# mainboardv3_4.net
KiCad netlist of a schematic drawn in EAGLE
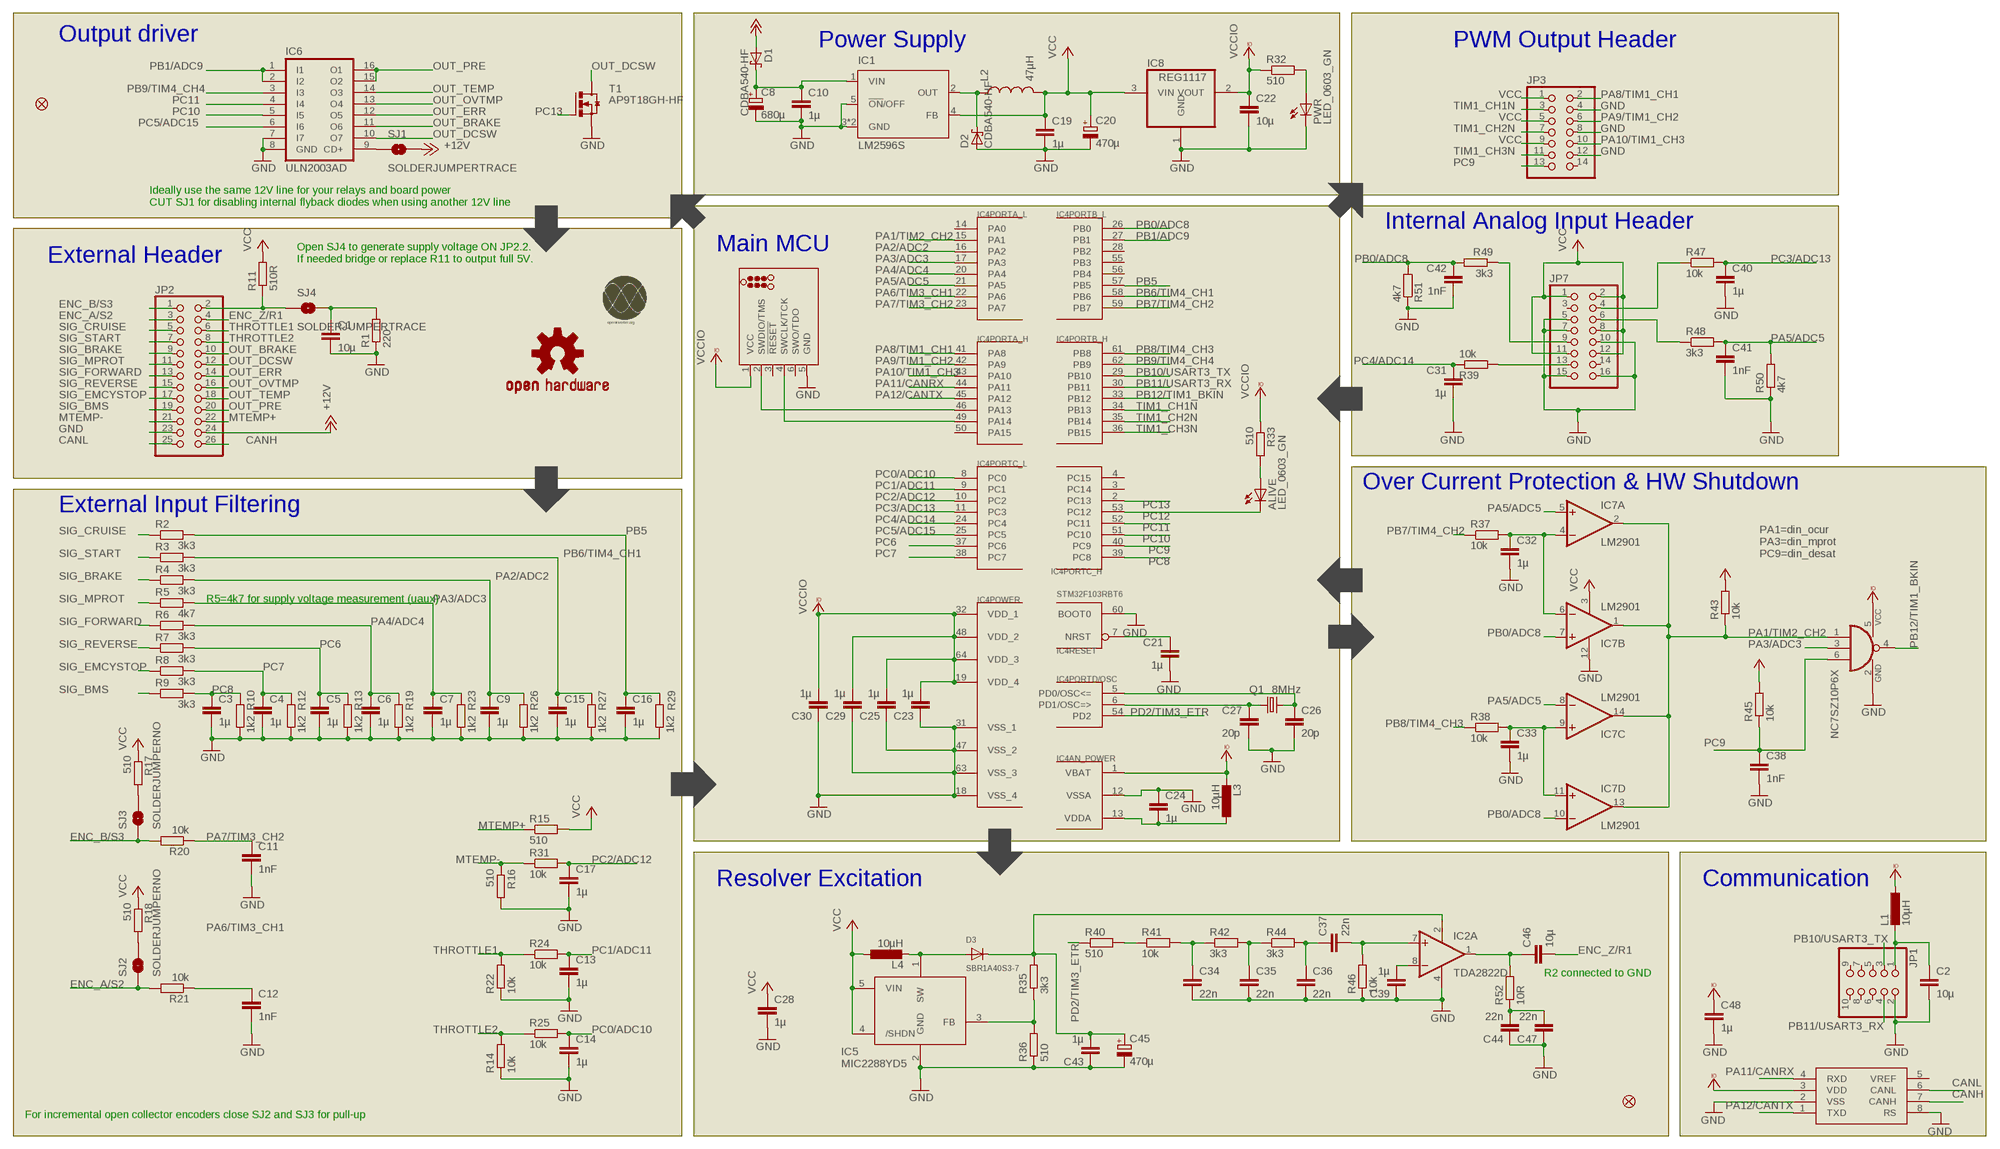
[diagram p0: schematic, sheet 1]

(export (version "E")
  (design (tool "Eeschema 10.0.6"))
  (components
    (comp (ref "ALIVE")
      (value "LED_0603_GN")
      (footprint "eagle-import:SML0805")
      (libsource (lib "eagle-import") (part "LEDSML0805"))
    )
    (comp (ref "C1")
      (value "10µ")
      (footprint "eagle-import:C0805")
      (libsource (lib "eagle-import") (part "C-EUC0805"))
    )
    (comp (ref "C2")
      (value "10µ")
      (footprint "eagle-import:C0805")
      (libsource (lib "eagle-import") (part "C-EUC0805"))
    )
    (comp (ref "C3")
      (value "1µ")
      (footprint "eagle-import:C0603")
      (libsource (lib "eagle-import") (part "C-EUC0603"))
    )
    (comp (ref "C4")
      (value "1µ")
      (footprint "eagle-import:C0603")
      (libsource (lib "eagle-import") (part "C-EUC0603"))
    )
    (comp (ref "C5")
      (value "1µ")
      (footprint "eagle-import:C0603")
      (libsource (lib "eagle-import") (part "C-EUC0603"))
    )
    (comp (ref "C6")
      (value "1µ")
      (footprint "eagle-import:C0603")
      (libsource (lib "eagle-import") (part "C-EUC0603"))
    )
    (comp (ref "C7")
      (value "1µ")
      (footprint "eagle-import:C0603")
      (libsource (lib "eagle-import") (part "C-EUC0603"))
    )
    (comp (ref "C8")
      (value "680µ")
      (footprint "eagle-import:UD-10X10_NICHICON")
      (libsource (lib "eagle-import") (part "CPOL-EUUD-10X10"))
    )
    (comp (ref "C9")
      (value "1µ")
      (footprint "eagle-import:C0603")
      (libsource (lib "eagle-import") (part "C-EUC0603"))
    )
    (comp (ref "C10")
      (value "1µ")
      (footprint "eagle-import:C0603")
      (libsource (lib "eagle-import") (part "C-EUC0603"))
    )
    (comp (ref "C11")
      (value "1nF")
      (footprint "eagle-import:C0603")
      (libsource (lib "eagle-import") (part "C-EUC0603"))
    )
    (comp (ref "C12")
      (value "1nF")
      (footprint "eagle-import:C0603")
      (libsource (lib "eagle-import") (part "C-EUC0603"))
    )
    (comp (ref "C13")
      (value "1µ")
      (footprint "eagle-import:C0603")
      (libsource (lib "eagle-import") (part "C-EUC0603"))
    )
    (comp (ref "C14")
      (value "1µ")
      (footprint "eagle-import:C0603")
      (libsource (lib "eagle-import") (part "C-EUC0603"))
    )
    (comp (ref "C15")
      (value "1µ")
      (footprint "eagle-import:C0603")
      (libsource (lib "eagle-import") (part "C-EUC0603"))
    )
    (comp (ref "C16")
      (value "1µ")
      (footprint "eagle-import:C0603")
      (libsource (lib "eagle-import") (part "C-EUC0603"))
    )
    (comp (ref "C17")
      (value "1µ")
      (footprint "eagle-import:C0603")
      (libsource (lib "eagle-import") (part "C-EUC0603"))
    )
    (comp (ref "C19")
      (value "1µ")
      (footprint "eagle-import:C0603")
      (libsource (lib "eagle-import") (part "C-EUC0603"))
    )
    (comp (ref "C20")
      (value "470µ")
      (footprint "eagle-import:UD-6,3X7,7_NICHICON")
      (libsource (lib "eagle-import") (part "CPOL-EUUD-6,3X7,7"))
    )
    (comp (ref "C21")
      (value "1µ")
      (footprint "eagle-import:C0603")
      (libsource (lib "eagle-import") (part "C-EUC0603"))
    )
    (comp (ref "C22")
      (value "10µ")
      (footprint "eagle-import:C0805")
      (libsource (lib "eagle-import") (part "C-EUC0805"))
    )
    (comp (ref "C23")
      (value "1µ")
      (footprint "eagle-import:C0603")
      (libsource (lib "eagle-import") (part "C-EUC0603"))
    )
    (comp (ref "C24")
      (value "1µ")
      (footprint "eagle-import:C0603")
      (libsource (lib "eagle-import") (part "C-EUC0603"))
    )
    (comp (ref "C25")
      (value "1µ")
      (footprint "eagle-import:C0603")
      (libsource (lib "eagle-import") (part "C-EUC0603"))
    )
    (comp (ref "C26")
      (value "20p")
      (footprint "eagle-import:C0603")
      (libsource (lib "eagle-import") (part "C-EUC0603"))
    )
    (comp (ref "C27")
      (value "20p")
      (footprint "eagle-import:C0603")
      (libsource (lib "eagle-import") (part "C-EUC0603"))
    )
    (comp (ref "C28")
      (value "1µ")
      (footprint "eagle-import:C0603")
      (libsource (lib "eagle-import") (part "C-EUC0603"))
    )
    (comp (ref "C29")
      (value "1µ")
      (footprint "eagle-import:C0603")
      (libsource (lib "eagle-import") (part "C-EUC0603"))
    )
    (comp (ref "C30")
      (value "1µ")
      (footprint "eagle-import:C0603")
      (libsource (lib "eagle-import") (part "C-EUC0603"))
    )
    (comp (ref "C31")
      (value "1µ")
      (footprint "eagle-import:C0603")
      (libsource (lib "eagle-import") (part "C-EUC0603"))
    )
    (comp (ref "C32")
      (value "1µ")
      (footprint "eagle-import:C0603")
      (libsource (lib "eagle-import") (part "C-EUC0603"))
    )
    (comp (ref "C33")
      (value "1µ")
      (footprint "eagle-import:C0603")
      (libsource (lib "eagle-import") (part "C-EUC0603"))
    )
    (comp (ref "C34")
      (value "22n")
      (footprint "eagle-import:C0603")
      (libsource (lib "eagle-import") (part "C-EUC0603"))
    )
    (comp (ref "C35")
      (value "22n")
      (footprint "eagle-import:C0603")
      (libsource (lib "eagle-import") (part "C-EUC0603"))
    )
    (comp (ref "C36")
      (value "22n")
      (footprint "eagle-import:C0603")
      (libsource (lib "eagle-import") (part "C-EUC0603"))
    )
    (comp (ref "C37")
      (value "22n")
      (footprint "eagle-import:C0603")
      (libsource (lib "eagle-import") (part "C-EUC0603"))
    )
    (comp (ref "C38")
      (value "1nF")
      (footprint "eagle-import:C0603")
      (libsource (lib "eagle-import") (part "C-EUC0603"))
    )
    (comp (ref "C39")
      (value "1µ")
      (footprint "eagle-import:C0603")
      (libsource (lib "eagle-import") (part "C-EUC0603"))
    )
    (comp (ref "C40")
      (value "1µ")
      (footprint "eagle-import:C0603")
      (libsource (lib "eagle-import") (part "C-EUC0603"))
    )
    (comp (ref "C41")
      (value "1nF")
      (footprint "eagle-import:C0603")
      (libsource (lib "eagle-import") (part "C-EUC0603"))
    )
    (comp (ref "C42")
      (value "1nF")
      (footprint "eagle-import:C0603")
      (libsource (lib "eagle-import") (part "C-EUC0603"))
    )
    (comp (ref "C43")
      (value "1µ")
      (footprint "eagle-import:C0603")
      (libsource (lib "eagle-import") (part "C-EUC0603"))
    )
    (comp (ref "C44")
      (value "22n")
      (footprint "eagle-import:C0603")
      (libsource (lib "eagle-import") (part "C-EUC0603"))
    )
    (comp (ref "C45")
      (value "470µ")
      (footprint "eagle-import:UD-6,3X7,7_NICHICON")
      (libsource (lib "eagle-import") (part "CPOL-EUUD-6,3X7,7"))
    )
    (comp (ref "C46")
      (value "10µ")
      (footprint "eagle-import:C0805")
      (libsource (lib "eagle-import") (part "C-EUC0805"))
    )
    (comp (ref "C47")
      (value "22n")
      (footprint "eagle-import:C0603")
      (libsource (lib "eagle-import") (part "C-EUC0603"))
    )
    (comp (ref "C48")
      (value "1µ")
      (footprint "eagle-import:C0603")
      (libsource (lib "eagle-import") (part "C-EUC0603"))
    )
    (comp (ref "D1")
      (value "CDBA540-HF")
      (footprint "eagle-import:SMB")
      (libsource (lib "eagle-import") (part "SCHOTTKY-DIODESMD"))
    )
    (comp (ref "D2")
      (value "CDBA540-HF")
      (footprint "eagle-import:SMB")
      (libsource (lib "eagle-import") (part "SCHOTTKY-DIODESMD"))
    )
    (comp (ref "D3")
      (value "SBR1A40S3-7")
      (footprint "eagle-import:SOD-323F")
      (libsource (lib "eagle-import") (part "DIODESOD-323F"))
    )
    (comp (ref "FID1")
      (value "FIDUCIAL1X2.5")
      (footprint "eagle-import:FIDUCIAL-1X2.5")
      (libsource (lib "eagle-import") (part "FIDUCIAL1X2.5"))
    )
    (comp (ref "FID2")
      (value "FIDUCIAL1X2.5")
      (footprint "eagle-import:FIDUCIAL-1X2.5")
      (libsource (lib "eagle-import") (part "FIDUCIAL1X2.5"))
    )
    (comp (ref "IC1")
      (value "LM2596S")
      (footprint "eagle-import:TO263-5")
      (fields (field (name "MF") "NATIONAL SEMICONDUCTOR") (field (name "MPN") "LM2596S-ADJ/NOPB"))
      (libsource (lib "eagle-import") (part "LM2596S"))
    )
    (comp (ref "IC2")
      (value "TDA2822D")
      (footprint "eagle-import:SO08")
      (libsource (lib "eagle-import") (part "TDA2822D"))
    )
    (comp (ref "IC3")
      (value "SN65HVD230DR")
      (footprint "eagle-import:SO08")
      (libsource (lib "eagle-import") (part "MCP2551"))
    )
    (comp (ref "IC4")
      (value "STM32F103RBT6")
      (footprint "eagle-import:TQFP64")
      (libsource (lib "eagle-import") (part "STM32F10XRXT6"))
    )
    (comp (ref "IC5")
      (value "MIC2288YD5")
      (footprint "eagle-import:SOT23-5L")
      (libsource (lib "eagle-import") (part "MIC2288YD5"))
    )
    (comp (ref "IC6")
      (value "ULN2003AD")
      (footprint "eagle-import:SO16")
      (libsource (lib "eagle-import") (part "ULN2003AD"))
    )
    (comp (ref "IC7")
      (value "LM2901")
      (footprint "eagle-import:SO14")
      (libsource (lib "eagle-import") (part "LM339D"))
    )
    (comp (ref "IC8")
      (value "REG1117")
      (footprint "eagle-import:SOT223")
      (libsource (lib "eagle-import") (part "REG1117"))
    )
    (comp (ref "IC9")
      (value "NC7SZ10P6X")
      (footprint "eagle-import:SC70-6")
      (libsource (lib "eagle-import") (part "741G10X"))
    )
    (comp (ref "J1")
      (value "TC2030_SWD-MCP")
      (footprint "eagle-import:TC2030-MCP")
      (libsource (lib "eagle-import") (part "TC2030_SWD-MCP"))
    )
    (comp (ref "JP1")
      (value "PINHD-2X5/90")
      (footprint "eagle-import:2X05_90")
      (libsource (lib "eagle-import") (part "PINHD-2X5/90"))
    )
    (comp (ref "JP2")
      (value "PINHD-2X13")
      (footprint "eagle-import:2X13")
      (libsource (lib "eagle-import") (part "PINHD-2X13"))
    )
    (comp (ref "JP3")
      (value "PINHD-2X7")
      (footprint "eagle-import:2X07")
      (libsource (lib "eagle-import") (part "PINHD-2X7"))
    )
    (comp (ref "JP7")
      (value "PINHD-2X8")
      (footprint "eagle-import:2X08")
      (libsource (lib "eagle-import") (part "PINHD-2X8"))
    )
    (comp (ref "L1")
      (value "10µH")
      (footprint "eagle-import:L2012C")
      (libsource (lib "eagle-import") (part "L-EUL2012C"))
    )
    (comp (ref "L2")
      (value "47µH")
      (footprint "eagle-import:CDRH125")
      (libsource (lib "eagle-import") (part "INDUCTORPWR"))
    )
    (comp (ref "L3")
      (value "10µH")
      (footprint "eagle-import:L2012C")
      (libsource (lib "eagle-import") (part "L-EUL2012C"))
    )
    (comp (ref "L4")
      (value "10µH")
      (footprint "eagle-import:L2825P")
      (libsource (lib "eagle-import") (part "L-EUL2825P"))
    )
    (comp (ref "LOGO1")
      (value "OSHW-LOGOM")
      (footprint "eagle-import:OSHW-LOGO-M")
      (libsource (lib "eagle-import") (part "OSHW-LOGOM"))
    )
    (comp (ref "PWR")
      (value "LED_0603_GN")
      (footprint "eagle-import:SML0805")
      (libsource (lib "eagle-import") (part "LEDSML0805"))
    )
    (comp (ref "Q1")
      (value "8MHz")
      (footprint "eagle-import:CRYSTAL-TXC-7A")
      (libsource (lib "eagle-import") (part "CRYSTALTXC-7A"))
    )
    (comp (ref "R1")
      (value "220")
      (footprint "eagle-import:R0603")
      (libsource (lib "eagle-import") (part "R-EU_R0603"))
    )
    (comp (ref "R2")
      (value "3k3")
      (footprint "eagle-import:R0603")
      (libsource (lib "eagle-import") (part "R-EU_R0603"))
    )
    (comp (ref "R3")
      (value "3k3")
      (footprint "eagle-import:R0603")
      (libsource (lib "eagle-import") (part "R-EU_R0603"))
    )
    (comp (ref "R4")
      (value "3k3")
      (footprint "eagle-import:R0603")
      (libsource (lib "eagle-import") (part "R-EU_R0603"))
    )
    (comp (ref "R5")
      (value "4k7")
      (footprint "eagle-import:R0603")
      (libsource (lib "eagle-import") (part "R-EU_R0603"))
    )
    (comp (ref "R6")
      (value "3k3")
      (footprint "eagle-import:R0603")
      (libsource (lib "eagle-import") (part "R-EU_R0603"))
    )
    (comp (ref "R7")
      (value "3k3")
      (footprint "eagle-import:R0603")
      (libsource (lib "eagle-import") (part "R-EU_R0603"))
    )
    (comp (ref "R8")
      (value "3k3")
      (footprint "eagle-import:R0603")
      (libsource (lib "eagle-import") (part "R-EU_R0603"))
    )
    (comp (ref "R9")
      (value "3k3")
      (footprint "eagle-import:R0603")
      (libsource (lib "eagle-import") (part "R-EU_R0603"))
    )
    (comp (ref "R10")
      (value "1k2")
      (footprint "eagle-import:R0603")
      (libsource (lib "eagle-import") (part "R-EU_R0603"))
    )
    (comp (ref "R11")
      (value "510R")
      (footprint "eagle-import:R0603")
      (libsource (lib "eagle-import") (part "R-EU_R0603"))
    )
    (comp (ref "R12")
      (value "1k2")
      (footprint "eagle-import:R0603")
      (libsource (lib "eagle-import") (part "R-EU_R0603"))
    )
    (comp (ref "R13")
      (value "1k2")
      (footprint "eagle-import:R0603")
      (libsource (lib "eagle-import") (part "R-EU_R0603"))
    )
    (comp (ref "R14")
      (value "10k")
      (footprint "eagle-import:R0603")
      (libsource (lib "eagle-import") (part "R-EU_R0603"))
    )
    (comp (ref "R15")
      (value "510")
      (footprint "eagle-import:R0603")
      (libsource (lib "eagle-import") (part "R-EU_R0603"))
    )
    (comp (ref "R16")
      (value "510")
      (footprint "eagle-import:R0603")
      (libsource (lib "eagle-import") (part "R-EU_R0603"))
    )
    (comp (ref "R17")
      (value "510")
      (footprint "eagle-import:R0603")
      (libsource (lib "eagle-import") (part "R-EU_R0603"))
    )
    (comp (ref "R18")
      (value "510")
      (footprint "eagle-import:R0603")
      (libsource (lib "eagle-import") (part "R-EU_R0603"))
    )
    (comp (ref "R19")
      (value "1k2")
      (footprint "eagle-import:R0603")
      (libsource (lib "eagle-import") (part "R-EU_R0603"))
    )
    (comp (ref "R20")
      (value "10k")
      (footprint "eagle-import:R0603")
      (libsource (lib "eagle-import") (part "R-EU_R0603"))
    )
    (comp (ref "R21")
      (value "10k")
      (footprint "eagle-import:R0603")
      (libsource (lib "eagle-import") (part "R-EU_R0603"))
    )
    (comp (ref "R22")
      (value "10k")
      (footprint "eagle-import:R0603")
      (libsource (lib "eagle-import") (part "R-EU_R0603"))
    )
    (comp (ref "R23")
      (value "1k2")
      (footprint "eagle-import:R0603")
      (libsource (lib "eagle-import") (part "R-EU_R0603"))
    )
    (comp (ref "R24")
      (value "10k")
      (footprint "eagle-import:R0603")
      (libsource (lib "eagle-import") (part "R-EU_R0603"))
    )
    (comp (ref "R25")
      (value "10k")
      (footprint "eagle-import:R0603")
      (libsource (lib "eagle-import") (part "R-EU_R0603"))
    )
    (comp (ref "R26")
      (value "1k2")
      (footprint "eagle-import:R0603")
      (libsource (lib "eagle-import") (part "R-EU_R0603"))
    )
    (comp (ref "R27")
      (value "1k2")
      (footprint "eagle-import:R0603")
      (libsource (lib "eagle-import") (part "R-EU_R0603"))
    )
    (comp (ref "R29")
      (value "1k2")
      (footprint "eagle-import:R0603")
      (libsource (lib "eagle-import") (part "R-EU_R0603"))
    )
    (comp (ref "R31")
      (value "10k")
      (footprint "eagle-import:R0603")
      (libsource (lib "eagle-import") (part "R-EU_R0603"))
    )
    (comp (ref "R32")
      (value "510")
      (footprint "eagle-import:R0603")
      (libsource (lib "eagle-import") (part "R-EU_R0603"))
    )
    (comp (ref "R33")
      (value "510")
      (footprint "eagle-import:R0603")
      (libsource (lib "eagle-import") (part "R-EU_R0603"))
    )
    (comp (ref "R35")
      (value "3k3")
      (footprint "eagle-import:R0603")
      (libsource (lib "eagle-import") (part "R-EU_R0603"))
    )
    (comp (ref "R36")
      (value "510")
      (footprint "eagle-import:R0603")
      (libsource (lib "eagle-import") (part "R-EU_R0603"))
    )
    (comp (ref "R37")
      (value "10k")
      (footprint "eagle-import:R0603")
      (libsource (lib "eagle-import") (part "R-EU_R0603"))
    )
    (comp (ref "R38")
      (value "10k")
      (footprint "eagle-import:R0603")
      (libsource (lib "eagle-import") (part "R-EU_R0603"))
    )
    (comp (ref "R39")
      (value "10k")
      (footprint "eagle-import:R0603")
      (libsource (lib "eagle-import") (part "R-EU_R0603"))
    )
    (comp (ref "R40")
      (value "510")
      (footprint "eagle-import:R0603")
      (libsource (lib "eagle-import") (part "R-EU_R0603"))
    )
    (comp (ref "R41")
      (value "10k")
      (footprint "eagle-import:R0603")
      (libsource (lib "eagle-import") (part "R-EU_R0603"))
    )
    (comp (ref "R42")
      (value "3k3")
      (footprint "eagle-import:R0603")
      (libsource (lib "eagle-import") (part "R-EU_R0603"))
    )
    (comp (ref "R43")
      (value "10k")
      (footprint "eagle-import:R0603")
      (libsource (lib "eagle-import") (part "R-EU_R0603"))
    )
    (comp (ref "R44")
      (value "3k3")
      (footprint "eagle-import:R0603")
      (libsource (lib "eagle-import") (part "R-EU_R0603"))
    )
    (comp (ref "R45")
      (value "10k")
      (footprint "eagle-import:R0603")
      (libsource (lib "eagle-import") (part "R-EU_R0603"))
    )
    (comp (ref "R46")
      (value "10k")
      (footprint "eagle-import:R0603")
      (libsource (lib "eagle-import") (part "R-EU_R0603"))
    )
    (comp (ref "R47")
      (value "10k")
      (footprint "eagle-import:R0603")
      (libsource (lib "eagle-import") (part "R-EU_R0603"))
    )
    (comp (ref "R48")
      (value "3k3")
      (footprint "eagle-import:R0603")
      (libsource (lib "eagle-import") (part "R-EU_R0603"))
    )
    (comp (ref "R49")
      (value "3k3")
      (footprint "eagle-import:R0603")
      (libsource (lib "eagle-import") (part "R-EU_R0603"))
    )
    (comp (ref "R50")
      (value "4k7")
      (footprint "eagle-import:R0603")
      (libsource (lib "eagle-import") (part "R-EU_R0603"))
    )
    (comp (ref "R51")
      (value "4k7")
      (footprint "eagle-import:R0603")
      (libsource (lib "eagle-import") (part "R-EU_R0603"))
    )
    (comp (ref "R52")
      (value "10R")
      (footprint "eagle-import:R0603")
      (libsource (lib "eagle-import") (part "R-EU_R0603"))
    )
    (comp (ref "SJ1")
      (value "SOLDERJUMPERTRACE")
      (footprint "eagle-import:SJ_2S-TRACE")
      (libsource (lib "eagle-import") (part "SOLDERJUMPERTRACE"))
    )
    (comp (ref "SJ2")
      (value "SOLDERJUMPERNO")
      (footprint "eagle-import:SJ_2S-NO")
      (libsource (lib "eagle-import") (part "SOLDERJUMPERNO"))
    )
    (comp (ref "SJ3")
      (value "SOLDERJUMPERNO")
      (footprint "eagle-import:SJ_2S-NO")
      (libsource (lib "eagle-import") (part "SOLDERJUMPERNO"))
    )
    (comp (ref "SJ4")
      (value "SOLDERJUMPERTRACE")
      (footprint "eagle-import:SJ_2S-TRACE")
      (libsource (lib "eagle-import") (part "SOLDERJUMPERTRACE"))
    )
    (comp (ref "T1")
      (value "AP9T18GH-HF")
      (footprint "eagle-import:D-PAK_TO252AA")
      (libsource (lib "eagle-import") (part "AP9T18GH-HF"))
    )
    (comp (ref "U$1")
      (value "OI-LOGO")
      (footprint "eagle-import:OI_LOGO")
      (libsource (lib "eagle-import") (part "OI-LOGO"))
    )
  )
  (nets
    (net (code "1") (name "+12V") (class "Default")
      (node (ref "D1") (pin "A") (pinfunction "A_A") (pintype "passive"))
      (node (ref "JP2") (pin "24") (pinfunction "24_24") (pintype "passive"))
      (node (ref "SJ1") (pin "2") (pinfunction "2_2") (pintype "passive"))
    )
    (net (code "2") (name "/CANH") (class "Default")
      (node (ref "IC3") (pin "7") (pinfunction "CANH_7") (pintype "bidirectional"))
      (node (ref "JP2") (pin "26") (pinfunction "26_26") (pintype "passive"))
    )
    (net (code "3") (name "/CANL") (class "Default")
      (node (ref "IC3") (pin "6") (pinfunction "CANL_6") (pintype "bidirectional"))
      (node (ref "JP2") (pin "25") (pinfunction "25_25") (pintype "passive"))
    )
    (net (code "4") (name "/ENC_A{slash}S2") (class "Default")
      (node (ref "JP2") (pin "3") (pinfunction "3_3") (pintype "passive"))
      (node (ref "R21") (pin "2") (pinfunction "2_2") (pintype "passive"))
      (node (ref "SJ2") (pin "1") (pinfunction "1_1") (pintype "passive"))
    )
    (net (code "5") (name "/ENC_B{slash}S3") (class "Default")
      (node (ref "JP2") (pin "1") (pinfunction "1_1") (pintype "passive"))
      (node (ref "R20") (pin "2") (pinfunction "2_2") (pintype "passive"))
      (node (ref "SJ3") (pin "1") (pinfunction "1_1") (pintype "passive"))
    )
    (net (code "6") (name "/ENC_Z{slash}R1") (class "Default")
      (node (ref "C46") (pin "2") (pinfunction "2_2") (pintype "passive"))
      (node (ref "JP2") (pin "4") (pinfunction "4_4") (pintype "passive"))
    )
    (net (code "7") (name "/MTEMP+") (class "Default")
      (node (ref "JP2") (pin "22") (pinfunction "22_22") (pintype "passive"))
      (node (ref "R15") (pin "1") (pinfunction "1_1") (pintype "passive"))
    )
    (net (code "8") (name "/MTEMP-") (class "Default")
      (node (ref "JP2") (pin "21") (pinfunction "21_21") (pintype "passive"))
      (node (ref "R16") (pin "1") (pinfunction "1_1") (pintype "passive"))
      (node (ref "R31") (pin "1") (pinfunction "1_1") (pintype "passive"))
    )
    (net (code "9") (name "/OUT_BRAKE") (class "Default")
      (node (ref "IC6") (pin "11") (pinfunction "O6_11") (pintype "open_collector"))
      (node (ref "JP2") (pin "10") (pinfunction "10_10") (pintype "passive"))
    )
    (net (code "10") (name "/OUT_DCSW") (class "Default")
      (node (ref "IC6") (pin "10") (pinfunction "O7_10") (pintype "open_collector"))
      (node (ref "JP2") (pin "12") (pinfunction "12_12") (pintype "passive"))
      (node (ref "T1") (pin "4") (pinfunction "D_4") (pintype "passive"))
    )
    (net (code "11") (name "/OUT_ERR") (class "Default")
      (node (ref "IC6") (pin "12") (pinfunction "O5_12") (pintype "open_collector"))
      (node (ref "JP2") (pin "14") (pinfunction "14_14") (pintype "passive"))
    )
    (net (code "12") (name "/OUT_OVTMP") (class "Default")
      (node (ref "IC6") (pin "13") (pinfunction "O4_13") (pintype "open_collector"))
      (node (ref "JP2") (pin "16") (pinfunction "16_16") (pintype "passive"))
    )
    (net (code "13") (name "/OUT_PRE") (class "Default")
      (node (ref "IC6") (pin "15") (pinfunction "O2_15") (pintype "open_collector"))
      (node (ref "IC6") (pin "16") (pinfunction "O1_16") (pintype "open_collector"))
      (node (ref "JP2") (pin "20") (pinfunction "20_20") (pintype "passive"))
    )
    (net (code "14") (name "/OUT_TEMP") (class "Default")
      (node (ref "IC6") (pin "14") (pinfunction "O3_14") (pintype "open_collector"))
      (node (ref "JP2") (pin "18") (pinfunction "18_18") (pintype "passive"))
    )
    (net (code "15") (name "/PA1{slash}TIM2_CH2") (class "Default")
      (node (ref "IC4") (pin "15") (pinfunction "PA1_15") (pintype "bidirectional"))
      (node (ref "IC7") (pin "1") (pinfunction "OUT_1") (pintype "open_collector"))
      (node (ref "IC7") (pin "13") (pinfunction "OUT_13") (pintype "open_collector"))
      (node (ref "IC7") (pin "14") (pinfunction "OUT_14") (pintype "open_collector"))
      (node (ref "IC7") (pin "2") (pinfunction "OUT_2") (pintype "open_collector"))
      (node (ref "IC9") (pin "1") (pinfunction "I0_1") (pintype "input"))
      (node (ref "R43") (pin "1") (pinfunction "1_1") (pintype "passive"))
    )
    (net (code "16") (name "/PA2{slash}ADC2") (class "Default")
      (node (ref "C9") (pin "1") (pinfunction "1_1") (pintype "passive"))
      (node (ref "IC4") (pin "16") (pinfunction "PA2_16") (pintype "bidirectional"))
      (node (ref "R26") (pin "2") (pinfunction "2_2") (pintype "passive"))
      (node (ref "R4") (pin "2") (pinfunction "2_2") (pintype "passive"))
    )
    (net (code "17") (name "/PA3{slash}ADC3") (class "Default")
      (node (ref "C7") (pin "1") (pinfunction "1_1") (pintype "passive"))
      (node (ref "IC4") (pin "17") (pinfunction "PA3_17") (pintype "bidirectional"))
      (node (ref "IC9") (pin "3") (pinfunction "I1_3") (pintype "input"))
      (node (ref "R23") (pin "2") (pinfunction "2_2") (pintype "passive"))
      (node (ref "R5") (pin "2") (pinfunction "2_2") (pintype "passive"))
    )
    (net (code "18") (name "/PA4{slash}ADC4") (class "Default")
      (node (ref "C6") (pin "1") (pinfunction "1_1") (pintype "passive"))
      (node (ref "IC4") (pin "20") (pinfunction "PA4_20") (pintype "bidirectional"))
      (node (ref "R19") (pin "2") (pinfunction "2_2") (pintype "passive"))
      (node (ref "R6") (pin "2") (pinfunction "2_2") (pintype "passive"))
    )
    (net (code "19") (name "/PA5{slash}ADC5") (class "Default")
      (node (ref "C41") (pin "1") (pinfunction "1_1") (pintype "passive"))
      (node (ref "IC4") (pin "21") (pinfunction "PA5_21") (pintype "bidirectional"))
      (node (ref "IC7") (pin "5") (pinfunction "+IN_5") (pintype "input"))
      (node (ref "IC7") (pin "8") (pinfunction "-IN_8") (pintype "input"))
      (node (ref "R48") (pin "2") (pinfunction "2_2") (pintype "passive"))
      (node (ref "R50") (pin "2") (pinfunction "2_2") (pintype "passive"))
    )
    (net (code "20") (name "/PA6{slash}TIM3_CH1") (class "Default")
      (node (ref "C12") (pin "1") (pinfunction "1_1") (pintype "passive"))
      (node (ref "IC4") (pin "22") (pinfunction "PA6_22") (pintype "bidirectional"))
      (node (ref "R21") (pin "1") (pinfunction "1_1") (pintype "passive"))
    )
    (net (code "21") (name "/PA7{slash}TIM3_CH2") (class "Default")
      (node (ref "C11") (pin "1") (pinfunction "1_1") (pintype "passive"))
      (node (ref "IC4") (pin "23") (pinfunction "PA7_23") (pintype "bidirectional"))
      (node (ref "R20") (pin "1") (pinfunction "1_1") (pintype "passive"))
    )
    (net (code "22") (name "/PA8{slash}TIM1_CH1") (class "Default")
      (node (ref "IC4") (pin "41") (pinfunction "PA8_41") (pintype "bidirectional"))
      (node (ref "JP3") (pin "2") (pinfunction "2_2") (pintype "passive"))
    )
    (net (code "23") (name "/PA9{slash}TIM1_CH2") (class "Default")
      (node (ref "IC4") (pin "42") (pinfunction "PA9_42") (pintype "bidirectional"))
      (node (ref "JP3") (pin "6") (pinfunction "6_6") (pintype "passive"))
    )
    (net (code "24") (name "/PA10{slash}TIM1_CH3") (class "Default")
      (node (ref "IC4") (pin "43") (pinfunction "PA10_43") (pintype "bidirectional"))
      (node (ref "JP3") (pin "10") (pinfunction "10_10") (pintype "passive"))
    )
    (net (code "25") (name "/PA11{slash}CANRX") (class "Default")
      (node (ref "IC3") (pin "4") (pinfunction "RXD_4") (pintype "bidirectional"))
      (node (ref "IC4") (pin "44") (pinfunction "PA11_44") (pintype "bidirectional"))
    )
    (net (code "26") (name "/PA12{slash}CANTX") (class "Default")
      (node (ref "IC3") (pin "1") (pinfunction "TXD_1") (pintype "bidirectional"))
      (node (ref "IC4") (pin "45") (pinfunction "PA12_45") (pintype "bidirectional"))
    )
    (net (code "27") (name "/PB0{slash}ADC8") (class "Default")
      (node (ref "C42") (pin "1") (pinfunction "1_1") (pintype "passive"))
      (node (ref "IC4") (pin "26") (pinfunction "PB0_26") (pintype "bidirectional"))
      (node (ref "IC7") (pin "10") (pinfunction "-IN_10") (pintype "input"))
      (node (ref "IC7") (pin "7") (pinfunction "+IN_7") (pintype "input"))
      (node (ref "R49") (pin "2") (pinfunction "2_2") (pintype "passive"))
      (node (ref "R51") (pin "2") (pinfunction "2_2") (pintype "passive"))
    )
    (net (code "28") (name "/PB1{slash}ADC9") (class "Default")
      (node (ref "IC4") (pin "27") (pinfunction "PB1_27") (pintype "bidirectional"))
      (node (ref "IC6") (pin "1") (pinfunction "I1_1") (pintype "input"))
      (node (ref "IC6") (pin "2") (pinfunction "I2_2") (pintype "input"))
    )
    (net (code "29") (name "/PB5") (class "Default")
      (node (ref "C16") (pin "1") (pinfunction "1_1") (pintype "passive"))
      (node (ref "IC4") (pin "57") (pinfunction "PB5_57") (pintype "bidirectional"))
      (node (ref "R2") (pin "2") (pinfunction "2_2") (pintype "passive"))
      (node (ref "R29") (pin "2") (pinfunction "2_2") (pintype "passive"))
    )
    (net (code "30") (name "/PB6{slash}TIM4_CH1") (class "Default")
      (node (ref "C15") (pin "1") (pinfunction "1_1") (pintype "passive"))
      (node (ref "IC4") (pin "58") (pinfunction "PB6_58") (pintype "bidirectional"))
      (node (ref "R27") (pin "2") (pinfunction "2_2") (pintype "passive"))
      (node (ref "R3") (pin "2") (pinfunction "2_2") (pintype "passive"))
    )
    (net (code "31") (name "/PB7{slash}TIM4_CH2") (class "Default")
      (node (ref "IC4") (pin "59") (pinfunction "PB7_59") (pintype "bidirectional"))
      (node (ref "R37") (pin "1") (pinfunction "1_1") (pintype "passive"))
    )
    (net (code "32") (name "/PB8{slash}TIM4_CH3") (class "Default")
      (node (ref "IC4") (pin "61") (pinfunction "PB8_61") (pintype "bidirectional"))
      (node (ref "R38") (pin "1") (pinfunction "1_1") (pintype "passive"))
    )
    (net (code "33") (name "/PB9{slash}TIM4_CH4") (class "Default")
      (node (ref "IC4") (pin "62") (pinfunction "PB9_62") (pintype "bidirectional"))
      (node (ref "IC6") (pin "3") (pinfunction "I3_3") (pintype "input"))
    )
    (net (code "34") (name "/PB10{slash}USART3_TX") (class "Default")
      (node (ref "IC4") (pin "29") (pinfunction "PB10_29") (pintype "bidirectional"))
      (node (ref "JP1") (pin "3") (pinfunction "3_3") (pintype "passive"))
    )
    (net (code "35") (name "/PB11{slash}USART3_RX") (class "Default")
      (node (ref "IC4") (pin "30") (pinfunction "PB11_30") (pintype "bidirectional"))
      (node (ref "JP1") (pin "4") (pinfunction "4_4") (pintype "passive"))
    )
    (net (code "36") (name "/PB12{slash}TIM1_BKIN") (class "Default")
      (node (ref "IC4") (pin "33") (pinfunction "PB12_33") (pintype "bidirectional"))
      (node (ref "IC9") (pin "4") (pinfunction "O_4") (pintype "open_collector"))
    )
    (net (code "37") (name "/PC0{slash}ADC10") (class "Default")
      (node (ref "C14") (pin "1") (pinfunction "1_1") (pintype "passive"))
      (node (ref "IC4") (pin "8") (pinfunction "PC0_8") (pintype "bidirectional"))
      (node (ref "R25") (pin "2") (pinfunction "2_2") (pintype "passive"))
    )
    (net (code "38") (name "/PC1{slash}ADC11") (class "Default")
      (node (ref "C13") (pin "1") (pinfunction "1_1") (pintype "passive"))
      (node (ref "IC4") (pin "9") (pinfunction "PC1_9") (pintype "bidirectional"))
      (node (ref "R24") (pin "2") (pinfunction "2_2") (pintype "passive"))
    )
    (net (code "39") (name "/PC2{slash}ADC12") (class "Default")
      (node (ref "C17") (pin "1") (pinfunction "1_1") (pintype "passive"))
      (node (ref "IC4") (pin "10") (pinfunction "PC2_10") (pintype "bidirectional"))
      (node (ref "R31") (pin "2") (pinfunction "2_2") (pintype "passive"))
    )
    (net (code "40") (name "/PC3{slash}ADC13") (class "Default")
      (node (ref "C40") (pin "1") (pinfunction "1_1") (pintype "passive"))
      (node (ref "IC4") (pin "11") (pinfunction "PC3_11") (pintype "bidirectional"))
      (node (ref "R47") (pin "2") (pinfunction "2_2") (pintype "passive"))
    )
    (net (code "41") (name "/PC4{slash}ADC14") (class "Default")
      (node (ref "C31") (pin "1") (pinfunction "1_1") (pintype "passive"))
      (node (ref "IC4") (pin "24") (pinfunction "PC4_24") (pintype "bidirectional"))
      (node (ref "R39") (pin "1") (pinfunction "1_1") (pintype "passive"))
    )
    (net (code "42") (name "/PC5{slash}ADC15") (class "Default")
      (node (ref "IC4") (pin "25") (pinfunction "PC5_25") (pintype "bidirectional"))
      (node (ref "IC6") (pin "6") (pinfunction "I6_6") (pintype "input"))
    )
    (net (code "43") (name "/PC6") (class "Default")
      (node (ref "C5") (pin "1") (pinfunction "1_1") (pintype "passive"))
      (node (ref "IC4") (pin "37") (pinfunction "PC6_37") (pintype "bidirectional"))
      (node (ref "R13") (pin "2") (pinfunction "2_2") (pintype "passive"))
      (node (ref "R7") (pin "2") (pinfunction "2_2") (pintype "passive"))
    )
    (net (code "44") (name "/PC7") (class "Default")
      (node (ref "C4") (pin "1") (pinfunction "1_1") (pintype "passive"))
      (node (ref "IC4") (pin "38") (pinfunction "PC7_38") (pintype "bidirectional"))
      (node (ref "R12") (pin "2") (pinfunction "2_2") (pintype "passive"))
      (node (ref "R8") (pin "2") (pinfunction "2_2") (pintype "passive"))
    )
    (net (code "45") (name "/PC8") (class "Default")
      (node (ref "C3") (pin "1") (pinfunction "1_1") (pintype "passive"))
      (node (ref "IC4") (pin "39") (pinfunction "PC8_39") (pintype "bidirectional"))
      (node (ref "R10") (pin "2") (pinfunction "2_2") (pintype "passive"))
      (node (ref "R9") (pin "2") (pinfunction "2_2") (pintype "passive"))
    )
    (net (code "46") (name "/PC9") (class "Default")
      (node (ref "C38") (pin "1") (pinfunction "1_1") (pintype "passive"))
      (node (ref "IC4") (pin "40") (pinfunction "PC9_40") (pintype "bidirectional"))
      (node (ref "IC9") (pin "6") (pinfunction "I2_6") (pintype "input"))
      (node (ref "JP3") (pin "13") (pinfunction "13_13") (pintype "passive"))
      (node (ref "R45") (pin "1") (pinfunction "1_1") (pintype "passive"))
    )
    (net (code "47") (name "/PC10") (class "Default")
      (node (ref "IC4") (pin "51") (pinfunction "PC10_51") (pintype "bidirectional"))
      (node (ref "IC6") (pin "5") (pinfunction "I5_5") (pintype "input"))
    )
    (net (code "48") (name "/PC11") (class "Default")
      (node (ref "IC4") (pin "52") (pinfunction "PC11_52") (pintype "bidirectional"))
      (node (ref "IC6") (pin "4") (pinfunction "I4_4") (pintype "input"))
    )
    (net (code "49") (name "/PC12") (class "Default")
      (node (ref "ALIVE") (pin "C") (pinfunction "C_C") (pintype "passive"))
      (node (ref "IC4") (pin "53") (pinfunction "PC12_53") (pintype "bidirectional"))
    )
    (net (code "50") (name "/PC13") (class "Default")
      (node (ref "IC4") (pin "2") (pinfunction "PC13_2") (pintype "bidirectional"))
      (node (ref "T1") (pin "1") (pinfunction "G_1") (pintype "passive"))
    )
    (net (code "51") (name "/PD2{slash}TIM3_ETR") (class "Default")
      (node (ref "IC4") (pin "54") (pinfunction "PD2_54") (pintype "bidirectional"))
      (node (ref "R40") (pin "1") (pinfunction "1_1") (pintype "passive"))
    )
    (net (code "52") (name "/SIG_BMS") (class "Default")
      (node (ref "JP2") (pin "19") (pinfunction "19_19") (pintype "passive"))
      (node (ref "R9") (pin "1") (pinfunction "1_1") (pintype "passive"))
    )
    (net (code "53") (name "/SIG_BRAKE") (class "Default")
      (node (ref "JP2") (pin "9") (pinfunction "9_9") (pintype "passive"))
      (node (ref "R4") (pin "1") (pinfunction "1_1") (pintype "passive"))
    )
    (net (code "54") (name "/SIG_CRUISE") (class "Default")
      (node (ref "JP2") (pin "5") (pinfunction "5_5") (pintype "passive"))
      (node (ref "R2") (pin "1") (pinfunction "1_1") (pintype "passive"))
    )
    (net (code "55") (name "/SIG_EMCYSTOP") (class "Default")
      (node (ref "JP2") (pin "17") (pinfunction "17_17") (pintype "passive"))
      (node (ref "R8") (pin "1") (pinfunction "1_1") (pintype "passive"))
    )
    (net (code "56") (name "/SIG_FORWARD") (class "Default")
      (node (ref "JP2") (pin "13") (pinfunction "13_13") (pintype "passive"))
      (node (ref "R6") (pin "1") (pinfunction "1_1") (pintype "passive"))
    )
    (net (code "57") (name "/SIG_MPROT") (class "Default")
      (node (ref "JP2") (pin "11") (pinfunction "11_11") (pintype "passive"))
      (node (ref "R5") (pin "1") (pinfunction "1_1") (pintype "passive"))
    )
    (net (code "58") (name "/SIG_REVERSE") (class "Default")
      (node (ref "JP2") (pin "15") (pinfunction "15_15") (pintype "passive"))
      (node (ref "R7") (pin "1") (pinfunction "1_1") (pintype "passive"))
    )
    (net (code "59") (name "/SIG_START") (class "Default")
      (node (ref "JP2") (pin "7") (pinfunction "7_7") (pintype "passive"))
      (node (ref "R3") (pin "1") (pinfunction "1_1") (pintype "passive"))
    )
    (net (code "60") (name "/THROTTLE1") (class "Default")
      (node (ref "JP2") (pin "6") (pinfunction "6_6") (pintype "passive"))
      (node (ref "R22") (pin "2") (pinfunction "2_2") (pintype "passive"))
      (node (ref "R24") (pin "1") (pinfunction "1_1") (pintype "passive"))
    )
    (net (code "61") (name "/THROTTLE2") (class "Default")
      (node (ref "JP2") (pin "8") (pinfunction "8_8") (pintype "passive"))
      (node (ref "R14") (pin "2") (pinfunction "2_2") (pintype "passive"))
      (node (ref "R25") (pin "1") (pinfunction "1_1") (pintype "passive"))
    )
    (net (code "62") (name "/TIM1_CH1N") (class "Default")
      (node (ref "IC4") (pin "34") (pinfunction "PB13_34") (pintype "bidirectional"))
      (node (ref "JP3") (pin "3") (pinfunction "3_3") (pintype "passive"))
    )
    (net (code "63") (name "/TIM1_CH2N") (class "Default")
      (node (ref "IC4") (pin "35") (pinfunction "PB14_35") (pintype "bidirectional"))
      (node (ref "JP3") (pin "7") (pinfunction "7_7") (pintype "passive"))
    )
    (net (code "64") (name "/TIM1_CH3N") (class "Default")
      (node (ref "IC4") (pin "36") (pinfunction "PB15_36") (pintype "bidirectional"))
      (node (ref "JP3") (pin "11") (pinfunction "11_11") (pintype "passive"))
    )
    (net (code "65") (name "GND") (class "Default")
      (node (ref "C1") (pin "2") (pinfunction "2_2") (pintype "passive"))
      (node (ref "C10") (pin "2") (pinfunction "2_2") (pintype "passive"))
      (node (ref "C11") (pin "2") (pinfunction "2_2") (pintype "passive"))
      (node (ref "C12") (pin "2") (pinfunction "2_2") (pintype "passive"))
      (node (ref "C13") (pin "2") (pinfunction "2_2") (pintype "passive"))
      (node (ref "C14") (pin "2") (pinfunction "2_2") (pintype "passive"))
      (node (ref "C15") (pin "2") (pinfunction "2_2") (pintype "passive"))
      (node (ref "C16") (pin "2") (pinfunction "2_2") (pintype "passive"))
      (node (ref "C17") (pin "2") (pinfunction "2_2") (pintype "passive"))
      (node (ref "C19") (pin "2") (pinfunction "2_2") (pintype "passive"))
      (node (ref "C2") (pin "2") (pinfunction "2_2") (pintype "passive"))
      (node (ref "C20") (pin "-") (pinfunction "-_-") (pintype "passive"))
      (node (ref "C21") (pin "2") (pinfunction "2_2") (pintype "passive"))
      (node (ref "C22") (pin "2") (pinfunction "2_2") (pintype "passive"))
      (node (ref "C23") (pin "1") (pinfunction "1_1") (pintype "passive"))
      (node (ref "C24") (pin "1") (pinfunction "1_1") (pintype "passive"))
      (node (ref "C25") (pin "1") (pinfunction "1_1") (pintype "passive"))
      (node (ref "C26") (pin "2") (pinfunction "2_2") (pintype "passive"))
      (node (ref "C27") (pin "2") (pinfunction "2_2") (pintype "passive"))
      (node (ref "C28") (pin "2") (pinfunction "2_2") (pintype "passive"))
      (node (ref "C29") (pin "1") (pinfunction "1_1") (pintype "passive"))
      (node (ref "C3") (pin "2") (pinfunction "2_2") (pintype "passive"))
      (node (ref "C30") (pin "1") (pinfunction "1_1") (pintype "passive"))
      (node (ref "C31") (pin "2") (pinfunction "2_2") (pintype "passive"))
      (node (ref "C32") (pin "2") (pinfunction "2_2") (pintype "passive"))
      (node (ref "C33") (pin "2") (pinfunction "2_2") (pintype "passive"))
      (node (ref "C34") (pin "2") (pinfunction "2_2") (pintype "passive"))
      (node (ref "C35") (pin "2") (pinfunction "2_2") (pintype "passive"))
      (node (ref "C36") (pin "2") (pinfunction "2_2") (pintype "passive"))
      (node (ref "C38") (pin "2") (pinfunction "2_2") (pintype "passive"))
      (node (ref "C39") (pin "1") (pinfunction "1_1") (pintype "passive"))
      (node (ref "C4") (pin "2") (pinfunction "2_2") (pintype "passive"))
      (node (ref "C40") (pin "2") (pinfunction "2_2") (pintype "passive"))
      (node (ref "C41") (pin "2") (pinfunction "2_2") (pintype "passive"))
      (node (ref "C42") (pin "2") (pinfunction "2_2") (pintype "passive"))
      (node (ref "C43") (pin "1") (pinfunction "1_1") (pintype "passive"))
      (node (ref "C44") (pin "1") (pinfunction "1_1") (pintype "passive"))
      (node (ref "C45") (pin "-") (pinfunction "-_-") (pintype "passive"))
      (node (ref "C47") (pin "1") (pinfunction "1_1") (pintype "passive"))
      (node (ref "C48") (pin "2") (pinfunction "2_2") (pintype "passive"))
      (node (ref "C5") (pin "2") (pinfunction "2_2") (pintype "passive"))
      (node (ref "C6") (pin "2") (pinfunction "2_2") (pintype "passive"))
      (node (ref "C7") (pin "2") (pinfunction "2_2") (pintype "passive"))
      (node (ref "C8") (pin "-") (pinfunction "-_-") (pintype "passive"))
      (node (ref "C9") (pin "2") (pinfunction "2_2") (pintype "passive"))
      (node (ref "D2") (pin "A") (pinfunction "A_A") (pintype "passive"))
      (node (ref "IC1") (pin "3") (pinfunction "GND_3") (pintype "power_in"))
      (node (ref "IC1") (pin "5") (pinfunction "~{ON}/OFF_5") (pintype "input"))
      (node (ref "IC1") (pin "6") (pinfunction "GND_6") (pintype "power_in"))
      (node (ref "IC2") (pin "4") (pinfunction "V-_4") (pintype "power_in"))
      (node (ref "IC3") (pin "2") (pinfunction "VSS_2") (pintype "bidirectional"))
      (node (ref "IC3") (pin "8") (pinfunction "RS_8") (pintype "bidirectional"))
      (node (ref "IC4") (pin "12") (pinfunction "VSSA_12") (pintype "power_in"))
      (node (ref "IC4") (pin "18") (pinfunction "VSS_4_18") (pintype "power_in"))
      (node (ref "IC4") (pin "31") (pinfunction "VSS_1_31") (pintype "power_in"))
      (node (ref "IC4") (pin "47") (pinfunction "VSS_2_47") (pintype "power_in"))
      (node (ref "IC4") (pin "60") (pinfunction "BOOT0_60") (pintype "input"))
      (node (ref "IC4") (pin "63") (pinfunction "VSS_3_63") (pintype "power_in"))
      (node (ref "IC5") (pin "2") (pinfunction "GND_2") (pintype "power_in"))
      (node (ref "IC6") (pin "7") (pinfunction "I7_7") (pintype "input"))
      (node (ref "IC6") (pin "8") (pinfunction "GND_8") (pintype "power_in"))
      (node (ref "IC7") (pin "12") (pinfunction "GND_12") (pintype "power_in"))
      (node (ref "IC8") (pin "1") (pinfunction "GND_1") (pintype "power_in"))
      (node (ref "IC9") (pin "2") (pinfunction "GND_2") (pintype "power_in"))
      (node (ref "J1") (pin "5") (pinfunction "GND_5") (pintype "passive"))
      (node (ref "JP1") (pin "2") (pinfunction "2_2") (pintype "passive"))
      (node (ref "JP2") (pin "23") (pinfunction "23_23") (pintype "passive"))
      (node (ref "JP3") (pin "12") (pinfunction "12_12") (pintype "passive"))
      (node (ref "JP3") (pin "4") (pinfunction "4_4") (pintype "passive"))
      (node (ref "JP3") (pin "8") (pinfunction "8_8") (pintype "passive"))
      (node (ref "JP7") (pin "10") (pinfunction "10_10") (pintype "passive"))
      (node (ref "JP7") (pin "15") (pinfunction "15_15") (pintype "passive"))
      (node (ref "JP7") (pin "16") (pinfunction "16_16") (pintype "passive"))
      (node (ref "JP7") (pin "5") (pinfunction "5_5") (pintype "passive"))
      (node (ref "JP7") (pin "7") (pinfunction "7_7") (pintype "passive"))
      (node (ref "PWR") (pin "C") (pinfunction "C_C") (pintype "passive"))
      (node (ref "R1") (pin "1") (pinfunction "1_1") (pintype "passive"))
      (node (ref "R10") (pin "1") (pinfunction "1_1") (pintype "passive"))
      (node (ref "R12") (pin "1") (pinfunction "1_1") (pintype "passive"))
      (node (ref "R13") (pin "1") (pinfunction "1_1") (pintype "passive"))
      (node (ref "R14") (pin "1") (pinfunction "1_1") (pintype "passive"))
      (node (ref "R16") (pin "2") (pinfunction "2_2") (pintype "passive"))
      (node (ref "R19") (pin "1") (pinfunction "1_1") (pintype "passive"))
      (node (ref "R22") (pin "1") (pinfunction "1_1") (pintype "passive"))
      (node (ref "R23") (pin "1") (pinfunction "1_1") (pintype "passive"))
      (node (ref "R26") (pin "1") (pinfunction "1_1") (pintype "passive"))
      (node (ref "R27") (pin "1") (pinfunction "1_1") (pintype "passive"))
      (node (ref "R29") (pin "1") (pinfunction "1_1") (pintype "passive"))
      (node (ref "R36") (pin "1") (pinfunction "1_1") (pintype "passive"))
      (node (ref "R46") (pin "1") (pinfunction "1_1") (pintype "passive"))
      (node (ref "R50") (pin "1") (pinfunction "1_1") (pintype "passive"))
      (node (ref "R51") (pin "1") (pinfunction "1_1") (pintype "passive"))
      (node (ref "T1") (pin "3") (pinfunction "S_3") (pintype "passive"))
    )
    (net (code "66") (name "Net-(ALIVE-PadA)") (class "Default")
      (node (ref "ALIVE") (pin "A") (pinfunction "A_A") (pintype "passive"))
      (node (ref "R33") (pin "2") (pinfunction "2_2") (pintype "passive"))
    )
    (net (code "67") (name "Net-(C1-Pad1)") (class "Default")
      (node (ref "C1") (pin "1") (pinfunction "1_1") (pintype "passive"))
      (node (ref "R1") (pin "2") (pinfunction "2_2") (pintype "passive"))
      (node (ref "SJ4") (pin "2") (pinfunction "2_2") (pintype "passive"))
    )
    (net (code "68") (name "Net-(C2-Pad1)") (class "Default")
      (node (ref "C2") (pin "1") (pinfunction "1_1") (pintype "passive"))
      (node (ref "JP1") (pin "1") (pinfunction "1_1") (pintype "passive"))
      (node (ref "L1") (pin "2") (pinfunction "2_2") (pintype "passive"))
    )
    (net (code "69") (name "Net-(C34-Pad1)") (class "Default")
      (node (ref "C34") (pin "1") (pinfunction "1_1") (pintype "passive"))
      (node (ref "R41") (pin "2") (pinfunction "2_2") (pintype "passive"))
      (node (ref "R42") (pin "1") (pinfunction "1_1") (pintype "passive"))
    )
    (net (code "70") (name "Net-(C35-Pad1)") (class "Default")
      (node (ref "C35") (pin "1") (pinfunction "1_1") (pintype "passive"))
      (node (ref "R42") (pin "2") (pinfunction "2_2") (pintype "passive"))
      (node (ref "R44") (pin "1") (pinfunction "1_1") (pintype "passive"))
    )
    (net (code "71") (name "Net-(C36-Pad1)") (class "Default")
      (node (ref "C36") (pin "1") (pinfunction "1_1") (pintype "passive"))
      (node (ref "C37") (pin "1") (pinfunction "1_1") (pintype "passive"))
      (node (ref "R44") (pin "2") (pinfunction "2_2") (pintype "passive"))
    )
    (net (code "72") (name "Net-(C44-Pad2)") (class "Default")
      (node (ref "C44") (pin "2") (pinfunction "2_2") (pintype "passive"))
      (node (ref "C47") (pin "2") (pinfunction "2_2") (pintype "passive"))
      (node (ref "R52") (pin "1") (pinfunction "1_1") (pintype "passive"))
    )
    (net (code "73") (name "Net-(IC1-OUT)") (class "Default")
      (node (ref "D2") (pin "C") (pinfunction "C_C") (pintype "passive"))
      (node (ref "IC1") (pin "2") (pinfunction "OUT_2") (pintype "output"))
      (node (ref "L2") (pin "1") (pinfunction "1_1") (pintype "passive"))
    )
    (net (code "74") (name "Net-(IC1-VIN)") (class "Default")
      (node (ref "C10") (pin "1") (pinfunction "1_1") (pintype "passive"))
      (node (ref "C8") (pin "+") (pinfunction "+_+") (pintype "passive"))
      (node (ref "D1") (pin "C") (pinfunction "C_C") (pintype "passive"))
      (node (ref "IC1") (pin "1") (pinfunction "VIN_1") (pintype "input"))
    )
    (net (code "75") (name "Net-(IC2A-+IN)") (class "Default")
      (node (ref "C37") (pin "2") (pinfunction "2_2") (pintype "passive"))
      (node (ref "IC2") (pin "7") (pinfunction "+IN_7") (pintype "input"))
      (node (ref "R46") (pin "2") (pinfunction "2_2") (pintype "passive"))
    )
    (net (code "76") (name "Net-(IC2A--IN)") (class "Default")
      (node (ref "C39") (pin "2") (pinfunction "2_2") (pintype "passive"))
      (node (ref "IC2") (pin "8") (pinfunction "-IN_8") (pintype "input"))
    )
    (net (code "77") (name "Net-(IC2A-OUT)") (class "Default")
      (node (ref "C46") (pin "1") (pinfunction "1_1") (pintype "passive"))
      (node (ref "IC2") (pin "1") (pinfunction "OUT_1") (pintype "output"))
      (node (ref "R52") (pin "2") (pinfunction "2_2") (pintype "passive"))
    )
    (net (code "78") (name "Net-(IC2C-V+)") (class "Default")
      (node (ref "C43") (pin "2") (pinfunction "2_2") (pintype "passive"))
      (node (ref "C45") (pin "+") (pinfunction "+_+") (pintype "passive"))
      (node (ref "D3") (pin "C") (pinfunction "C_C") (pintype "passive"))
      (node (ref "IC2") (pin "2") (pinfunction "V+_2") (pintype "power_in"))
      (node (ref "R35") (pin "2") (pinfunction "2_2") (pintype "passive"))
    )
    (net (code "79") (name "Net-(IC4A-VDDA)") (class "Default")
      (node (ref "C24") (pin "2") (pinfunction "2_2") (pintype "passive"))
      (node (ref "IC4") (pin "13") (pinfunction "VDDA_13") (pintype "power_in"))
      (node (ref "L3") (pin "1") (pinfunction "1_1") (pintype "passive"))
    )
    (net (code "80") (name "Net-(IC4B-PA13)") (class "Default")
      (node (ref "IC4") (pin "46") (pinfunction "PA13_46") (pintype "bidirectional"))
      (node (ref "J1") (pin "2") (pinfunction "SWDIO/TMS_2") (pintype "bidirectional"))
    )
    (net (code "81") (name "Net-(IC4B-PA14)") (class "Default")
      (node (ref "IC4") (pin "49") (pinfunction "PA14_49") (pintype "bidirectional"))
      (node (ref "J1") (pin "4") (pinfunction "SWCLK/TCK_4") (pintype "output"))
    )
    (net (code "82") (name "Net-(IC4H-PD0{slash}OSC<=)") (class "Default")
      (node (ref "C26") (pin "1") (pinfunction "1_1") (pintype "passive"))
      (node (ref "IC4") (pin "5") (pinfunction "PD0/OSC<=_5") (pintype "bidirectional"))
      (node (ref "Q1") (pin "P$2") (pinfunction "2_P$2") (pintype "passive"))
    )
    (net (code "83") (name "Net-(IC4H-PD1{slash}OSC=>)") (class "Default")
      (node (ref "C27") (pin "1") (pinfunction "1_1") (pintype "passive"))
      (node (ref "IC4") (pin "6") (pinfunction "PD1/OSC=>_6") (pintype "bidirectional"))
      (node (ref "Q1") (pin "P$1") (pinfunction "1_P$1") (pintype "passive"))
    )
    (net (code "84") (name "Net-(IC4J-NRST)") (class "Default")
      (node (ref "C21") (pin "1") (pinfunction "1_1") (pintype "passive"))
      (node (ref "IC4") (pin "7") (pinfunction "NRST_7") (pintype "input"))
    )
    (net (code "85") (name "Net-(IC5-FB)") (class "Default")
      (node (ref "IC5") (pin "3") (pinfunction "FB_3") (pintype "input"))
      (node (ref "R35") (pin "1") (pinfunction "1_1") (pintype "passive"))
      (node (ref "R36") (pin "2") (pinfunction "2_2") (pintype "passive"))
    )
    (net (code "86") (name "Net-(IC5-SW)") (class "Default")
      (node (ref "D3") (pin "A") (pinfunction "A_A") (pintype "passive"))
      (node (ref "IC5") (pin "1") (pinfunction "SW_1") (pintype "output"))
      (node (ref "L4") (pin "2") (pinfunction "2_2") (pintype "passive"))
    )
    (net (code "87") (name "Net-(IC6-CD+)") (class "Default")
      (node (ref "IC6") (pin "9") (pinfunction "CD+_9") (pintype "passive"))
      (node (ref "SJ1") (pin "1") (pinfunction "1_1") (pintype "passive"))
    )
    (net (code "88") (name "Net-(IC7A--IN)") (class "Default")
      (node (ref "C32") (pin "1") (pinfunction "1_1") (pintype "passive"))
      (node (ref "IC7") (pin "4") (pinfunction "-IN_4") (pintype "input"))
      (node (ref "IC7") (pin "6") (pinfunction "-IN_6") (pintype "input"))
      (node (ref "R37") (pin "2") (pinfunction "2_2") (pintype "passive"))
    )
    (net (code "89") (name "Net-(IC7C-+IN)") (class "Default")
      (node (ref "C33") (pin "1") (pinfunction "1_1") (pintype "passive"))
      (node (ref "IC7") (pin "11") (pinfunction "+IN_11") (pintype "input"))
      (node (ref "IC7") (pin "9") (pinfunction "+IN_9") (pintype "input"))
      (node (ref "R38") (pin "2") (pinfunction "2_2") (pintype "passive"))
    )
    (net (code "90") (name "Net-(JP2-Pad2)") (class "Default")
      (node (ref "JP2") (pin "2") (pinfunction "2_2") (pintype "passive"))
      (node (ref "R11") (pin "1") (pinfunction "1_1") (pintype "passive"))
      (node (ref "SJ4") (pin "1") (pinfunction "1_1") (pintype "passive"))
    )
    (net (code "91") (name "Net-(JP7-Pad4)") (class "Default")
      (node (ref "JP7") (pin "4") (pinfunction "4_4") (pintype "passive"))
      (node (ref "R47") (pin "1") (pinfunction "1_1") (pintype "passive"))
    )
    (net (code "92") (name "Net-(JP7-Pad6)") (class "Default")
      (node (ref "JP7") (pin "6") (pinfunction "6_6") (pintype "passive"))
      (node (ref "R48") (pin "1") (pinfunction "1_1") (pintype "passive"))
    )
    (net (code "93") (name "Net-(JP7-Pad9)") (class "Default")
      (node (ref "JP7") (pin "9") (pinfunction "9_9") (pintype "passive"))
      (node (ref "R49") (pin "1") (pinfunction "1_1") (pintype "passive"))
    )
    (net (code "94") (name "Net-(JP7-Pad13)") (class "Default")
      (node (ref "JP7") (pin "13") (pinfunction "13_13") (pintype "passive"))
      (node (ref "R39") (pin "2") (pinfunction "2_2") (pintype "passive"))
    )
    (net (code "95") (name "Net-(PWR-PadA)") (class "Default")
      (node (ref "PWR") (pin "A") (pinfunction "A_A") (pintype "passive"))
      (node (ref "R32") (pin "2") (pinfunction "2_2") (pintype "passive"))
    )
    (net (code "96") (name "Net-(R17-Pad2)") (class "Default")
      (node (ref "R17") (pin "2") (pinfunction "2_2") (pintype "passive"))
      (node (ref "SJ3") (pin "2") (pinfunction "2_2") (pintype "passive"))
    )
    (net (code "97") (name "Net-(R18-Pad2)") (class "Default")
      (node (ref "R18") (pin "2") (pinfunction "2_2") (pintype "passive"))
      (node (ref "SJ2") (pin "2") (pinfunction "2_2") (pintype "passive"))
    )
    (net (code "98") (name "Net-(R40-Pad2)") (class "Default")
      (node (ref "R40") (pin "2") (pinfunction "2_2") (pintype "passive"))
      (node (ref "R41") (pin "1") (pinfunction "1_1") (pintype "passive"))
    )
    (net (code "99") (name "VCC") (class "Default")
      (node (ref "C19") (pin "1") (pinfunction "1_1") (pintype "passive"))
      (node (ref "C20") (pin "+") (pinfunction "+_+") (pintype "passive"))
      (node (ref "C28") (pin "1") (pinfunction "1_1") (pintype "passive"))
      (node (ref "IC1") (pin "4") (pinfunction "FB_4") (pintype "input"))
      (node (ref "IC5") (pin "4") (pinfunction "/SHDN_4") (pintype "input"))
      (node (ref "IC5") (pin "5") (pinfunction "VIN_5") (pintype "input"))
      (node (ref "IC7") (pin "3") (pinfunction "V+_3") (pintype "power_in"))
      (node (ref "IC8") (pin "3") (pinfunction "VIN_3") (pintype "input"))
      (node (ref "JP3") (pin "1") (pinfunction "1_1") (pintype "passive"))
      (node (ref "JP3") (pin "5") (pinfunction "5_5") (pintype "passive"))
      (node (ref "JP3") (pin "9") (pinfunction "9_9") (pintype "passive"))
      (node (ref "JP7") (pin "1") (pinfunction "1_1") (pintype "passive"))
      (node (ref "JP7") (pin "11") (pinfunction "11_11") (pintype "passive"))
      (node (ref "JP7") (pin "12") (pinfunction "12_12") (pintype "passive"))
      (node (ref "JP7") (pin "2") (pinfunction "2_2") (pintype "passive"))
      (node (ref "JP7") (pin "8") (pinfunction "8_8") (pintype "passive"))
      (node (ref "L2") (pin "2") (pinfunction "2_2") (pintype "passive"))
      (node (ref "L4") (pin "1") (pinfunction "1_1") (pintype "passive"))
      (node (ref "R11") (pin "2") (pinfunction "2_2") (pintype "passive"))
      (node (ref "R15") (pin "2") (pinfunction "2_2") (pintype "passive"))
      (node (ref "R17") (pin "1") (pinfunction "1_1") (pintype "passive"))
      (node (ref "R18") (pin "1") (pinfunction "1_1") (pintype "passive"))
      (node (ref "R43") (pin "2") (pinfunction "2_2") (pintype "passive"))
      (node (ref "R45") (pin "2") (pinfunction "2_2") (pintype "passive"))
    )
    (net (code "100") (name "VCCIO") (class "Default")
      (node (ref "C22") (pin "1") (pinfunction "1_1") (pintype "passive"))
      (node (ref "C23") (pin "2") (pinfunction "2_2") (pintype "passive"))
      (node (ref "C25") (pin "2") (pinfunction "2_2") (pintype "passive"))
      (node (ref "C29") (pin "2") (pinfunction "2_2") (pintype "passive"))
      (node (ref "C30") (pin "2") (pinfunction "2_2") (pintype "passive"))
      (node (ref "C48") (pin "1") (pinfunction "1_1") (pintype "passive"))
      (node (ref "IC3") (pin "3") (pinfunction "VDD_3") (pintype "bidirectional"))
      (node (ref "IC4") (pin "1") (pinfunction "VBAT_1") (pintype "power_in"))
      (node (ref "IC4") (pin "19") (pinfunction "VDD_4_19") (pintype "power_in"))
      (node (ref "IC4") (pin "32") (pinfunction "VDD_1_32") (pintype "power_in"))
      (node (ref "IC4") (pin "48") (pinfunction "VDD_2_48") (pintype "power_in"))
      (node (ref "IC4") (pin "64") (pinfunction "VDD_3_64") (pintype "power_in"))
      (node (ref "IC8") (pin "2") (pinfunction "VOUT_2") (pintype "output"))
      (node (ref "IC9") (pin "5") (pinfunction "VCC_5") (pintype "power_in"))
      (node (ref "J1") (pin "1") (pinfunction "VCC_1") (pintype "passive"))
      (node (ref "L1") (pin "1") (pinfunction "1_1") (pintype "passive"))
      (node (ref "L3") (pin "2") (pinfunction "2_2") (pintype "passive"))
      (node (ref "R32") (pin "1") (pinfunction "1_1") (pintype "passive"))
      (node (ref "R33") (pin "1") (pinfunction "1_1") (pintype "passive"))
    )
    (net (code "101") (name "unconnected-(IC3-VREF-Pad5)") (class "Default")
      (node (ref "IC3") (pin "5") (pinfunction "VREF_5") (pintype "bidirectional"))
    )
    (net (code "102") (name "unconnected-(IC4B-PA15-Pad50)") (class "Default")
      (node (ref "IC4") (pin "50") (pinfunction "PA15_50") (pintype "bidirectional"))
    )
    (net (code "103") (name "unconnected-(IC4C-PA0-Pad14)") (class "Default")
      (node (ref "IC4") (pin "14") (pinfunction "PA0_14") (pintype "bidirectional"))
    )
    (net (code "104") (name "unconnected-(IC4E-PB2-Pad28)") (class "Default")
      (node (ref "IC4") (pin "28") (pinfunction "PB2_28") (pintype "bidirectional"))
    )
    (net (code "105") (name "unconnected-(IC4E-PB3-Pad55)") (class "Default")
      (node (ref "IC4") (pin "55") (pinfunction "PB3_55") (pintype "bidirectional"))
    )
    (net (code "106") (name "unconnected-(IC4E-PB4-Pad56)") (class "Default")
      (node (ref "IC4") (pin "56") (pinfunction "PB4_56") (pintype "bidirectional"))
    )
    (net (code "107") (name "unconnected-(IC4F-PC14-Pad3)") (class "Default")
      (node (ref "IC4") (pin "3") (pinfunction "PC14_3") (pintype "bidirectional"))
    )
    (net (code "108") (name "unconnected-(IC4F-PC15-Pad4)") (class "Default")
      (node (ref "IC4") (pin "4") (pinfunction "PC15_4") (pintype "bidirectional"))
    )
    (net (code "109") (name "unconnected-(J1-SWO{slash}TDO-Pad6)") (class "Default")
      (node (ref "J1") (pin "6") (pinfunction "SWO/TDO_6") (pintype "bidirectional"))
    )
    (net (code "110") (name "unconnected-(J1-~{RESET}-Pad3)") (class "Default")
      (node (ref "J1") (pin "3") (pinfunction "~{RESET}_3") (pintype "output"))
    )
    (net (code "111") (name "unconnected-(JP1-Pad5)") (class "Default")
      (node (ref "JP1") (pin "5") (pinfunction "5_5") (pintype "passive"))
    )
    (net (code "112") (name "unconnected-(JP1-Pad6)") (class "Default")
      (node (ref "JP1") (pin "6") (pinfunction "6_6") (pintype "passive"))
    )
    (net (code "113") (name "unconnected-(JP1-Pad7)") (class "Default")
      (node (ref "JP1") (pin "7") (pinfunction "7_7") (pintype "passive"))
    )
    (net (code "114") (name "unconnected-(JP1-Pad8)") (class "Default")
      (node (ref "JP1") (pin "8") (pinfunction "8_8") (pintype "passive"))
    )
    (net (code "115") (name "unconnected-(JP1-Pad9)") (class "Default")
      (node (ref "JP1") (pin "9") (pinfunction "9_9") (pintype "passive"))
    )
    (net (code "116") (name "unconnected-(JP1-Pad10)") (class "Default")
      (node (ref "JP1") (pin "10") (pinfunction "10_10") (pintype "passive"))
    )
    (net (code "117") (name "unconnected-(JP3-Pad14)") (class "Default")
      (node (ref "JP3") (pin "14") (pinfunction "14_14") (pintype "passive"))
    )
    (net (code "118") (name "unconnected-(JP7-Pad3)") (class "Default")
      (node (ref "JP7") (pin "3") (pinfunction "3_3") (pintype "passive"))
    )
    (net (code "119") (name "unconnected-(JP7-Pad14)") (class "Default")
      (node (ref "JP7") (pin "14") (pinfunction "14_14") (pintype "passive"))
    )
  )
)
